# partial_vna.net
KiCad netlist of a schematic drawn in Altium Designer
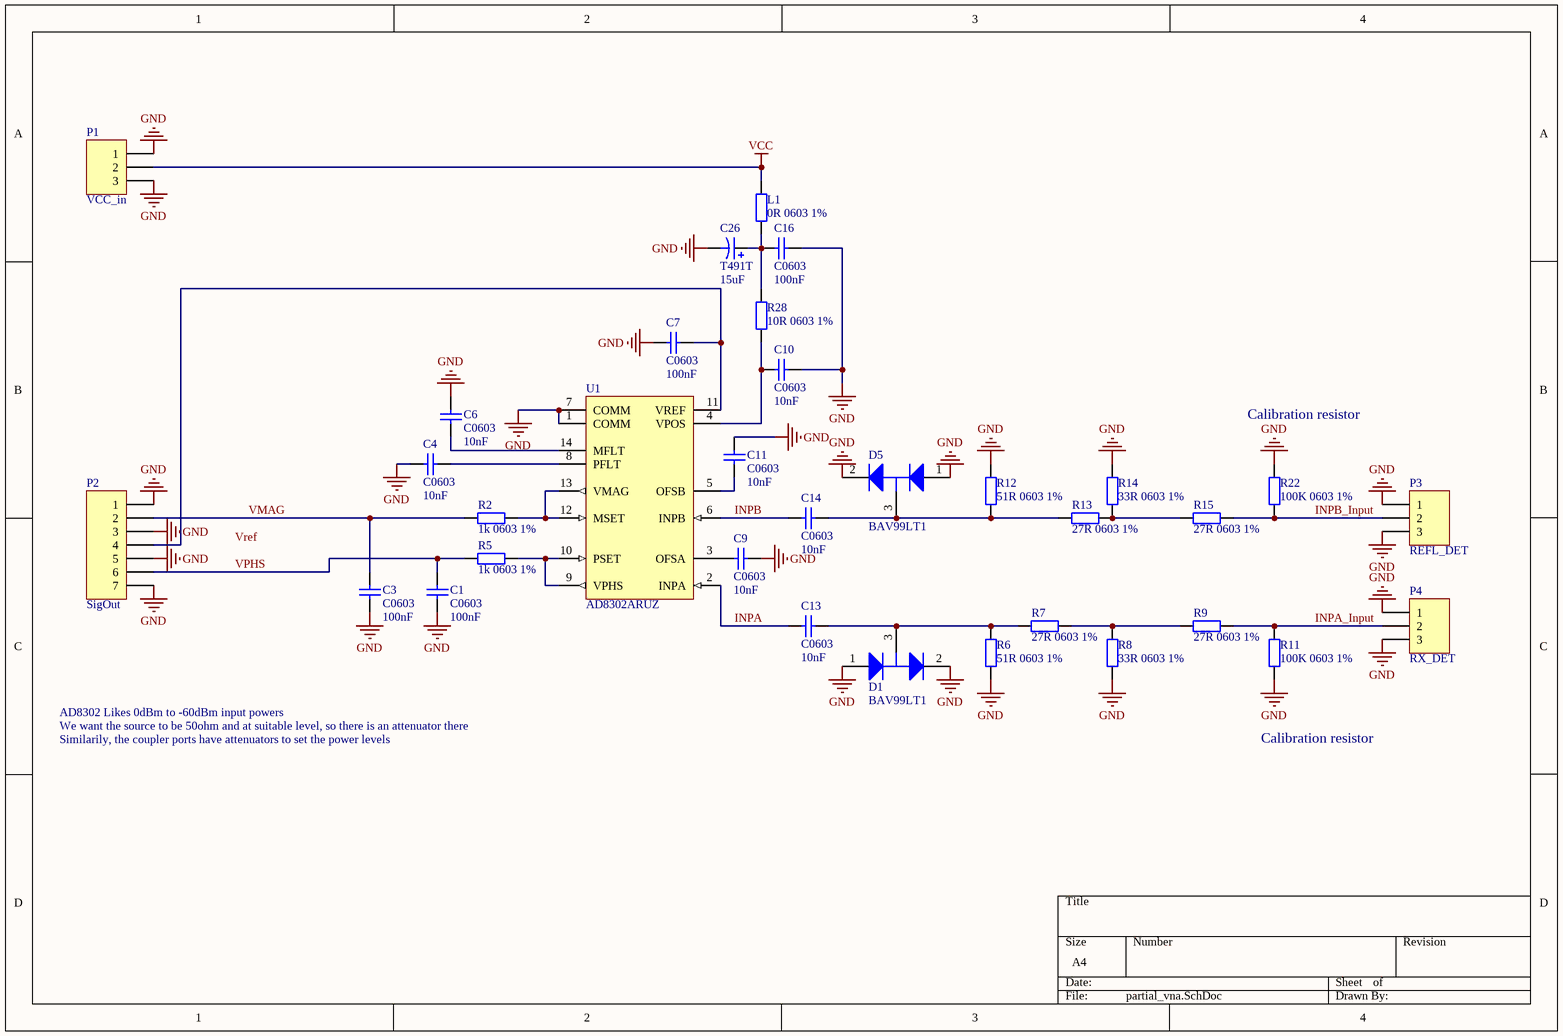
[diagram p0: partial_vna.SchDoc]

(export (version "E")
  (design (tool "Eeschema 10.0.6"))
  (components
    (comp (ref "C1")
      (value "C0603")
      (footprint "0603")
      (description "Ceramic Chip Capacitor - Standard")
      (fields (field (name "ALTIUM_VALUE") "100nF") (field (name "PUBLISHER") "Altium Limited"))
      (libsource (lib "KEMET Chip Capacitor") (part "C0603"))
    )
    (comp (ref "C3")
      (value "C0603")
      (footprint "0603")
      (description "Ceramic Chip Capacitor - Standard")
      (fields (field (name "ALTIUM_VALUE") "100nF") (field (name "PUBLISHER") "Altium Limited"))
      (libsource (lib "KEMET Chip Capacitor") (part "C0603"))
    )
    (comp (ref "C4")
      (value "C0603")
      (footprint "0603")
      (description "Ceramic Chip Capacitor - Standard")
      (fields (field (name "ALTIUM_VALUE") "10nF") (field (name "PUBLISHER") "Altium Limited"))
      (libsource (lib "KEMET Chip Capacitor") (part "C0603"))
    )
    (comp (ref "C6")
      (value "C0603")
      (footprint "0603")
      (description "Ceramic Chip Capacitor - Standard")
      (fields (field (name "ALTIUM_VALUE") "10nF") (field (name "PUBLISHER") "Altium Limited"))
      (libsource (lib "KEMET Chip Capacitor") (part "C0603"))
    )
    (comp (ref "C7")
      (value "C0603")
      (footprint "0603")
      (description "Ceramic Chip Capacitor - Standard")
      (fields (field (name "ALTIUM_VALUE") "100nF") (field (name "PUBLISHER") "Altium Limited"))
      (libsource (lib "KEMET Chip Capacitor") (part "C0603"))
    )
    (comp (ref "C9")
      (value "C0603")
      (footprint "0603")
      (description "Ceramic Chip Capacitor - Standard")
      (fields (field (name "ALTIUM_VALUE") "10nF") (field (name "PUBLISHER") "Altium Limited"))
      (libsource (lib "KEMET Chip Capacitor") (part "C0603"))
    )
    (comp (ref "C10")
      (value "C0603")
      (footprint "0603")
      (description "Ceramic Chip Capacitor - Standard")
      (fields (field (name "ALTIUM_VALUE") "10nF") (field (name "PUBLISHER") "Altium Limited"))
      (libsource (lib "KEMET Chip Capacitor") (part "C0603"))
    )
    (comp (ref "C11")
      (value "C0603")
      (footprint "0603")
      (description "Ceramic Chip Capacitor - Standard")
      (fields (field (name "ALTIUM_VALUE") "10nF") (field (name "PUBLISHER") "Altium Limited"))
      (libsource (lib "KEMET Chip Capacitor") (part "C0603"))
    )
    (comp (ref "C13")
      (value "C0603")
      (footprint "0603")
      (description "Ceramic Chip Capacitor - Standard")
      (fields (field (name "ALTIUM_VALUE") "10nF") (field (name "PUBLISHER") "Altium Limited"))
      (libsource (lib "KEMET Chip Capacitor") (part "C0603"))
    )
    (comp (ref "C14")
      (value "C0603")
      (footprint "0603")
      (description "Ceramic Chip Capacitor - Standard")
      (fields (field (name "ALTIUM_VALUE") "10nF") (field (name "PUBLISHER") "Altium Limited"))
      (libsource (lib "KEMET Chip Capacitor") (part "C0603"))
    )
    (comp (ref "C16")
      (value "C0603")
      (footprint "0603")
      (description "Ceramic Chip Capacitor - Standard")
      (fields (field (name "ALTIUM_VALUE") "100nF") (field (name "PUBLISHER") "Altium Limited"))
      (libsource (lib "KEMET Chip Capacitor") (part "C0603"))
    )
    (comp (ref "C26")
      (value "T491T")
      (footprint "T")
      (description "Solid Tantalum Chip Capacitor, Low Profile T491 Series - Industrial Grade")
      (fields (field (name "ALTIUM_VALUE") "15uF") (field (name "PUBLISHER") "Altium Limited"))
      (libsource (lib "KEMET Chip Capacitor") (part "T491T"))
    )
    (comp (ref "D1")
      (value "BAV99LT1")
      (footprint "ONSC-SOT-23-3-318-08_V")
      (description "Dual Series Switching Diodes, 3-Pin SOT-23, Tape and Reel")
      (fields (field (name "MANUFACTURER") "On Semiconductor"))
      (libsource (lib "ON Semi Small Signal Switching Diodes") (part "BAV99LT1"))
    )
    (comp (ref "D5")
      (value "BAV99LT1")
      (footprint "ONSC-SOT-23-3-318-08_V")
      (description "Dual Series Switching Diodes, 3-Pin SOT-23, Tape and Reel")
      (fields (field (name "MANUFACTURER") "On Semiconductor"))
      (libsource (lib "ON Semi Small Signal Switching Diodes") (part "BAV99LT1"))
    )
    (comp (ref "L1")
      (value "0R 0603 1%")
      (footprint "R0603")
      (fields (field (name "TOLERANCE") "1%") (field (name "PUBLISHER") "iv"))
      (libsource (lib "ftg_lib") (part "0R 0603"))
    )
    (comp (ref "P1")
      (value "VCC_in")
      (footprint "HDR1X3")
      (description "Header, 3-Pin")
      (fields (field (name "PUBLISHER") "Altium Limited"))
      (libsource (lib "") (part "Header 3_1"))
    )
    (comp (ref "P2")
      (value "SigOut")
      (footprint "HDR1X7")
      (description "Header, 7-Pin")
      (fields (field (name "PUBLISHER") "Altium Limited"))
      (libsource (lib "Miscellaneous Connectors") (part "Header 7"))
    )
    (comp (ref "P3")
      (value "REFL_DET")
      (footprint "HDR1X3")
      (description "Header, 3-Pin")
      (fields (field (name "PUBLISHER") "Altium Limited"))
      (libsource (lib "Miscellaneous Connectors") (part "Header 3"))
    )
    (comp (ref "P4")
      (value "RX_DET")
      (footprint "HDR1X3")
      (description "Header, 3-Pin")
      (fields (field (name "PUBLISHER") "Altium Limited"))
      (libsource (lib "Miscellaneous Connectors") (part "Header 3"))
    )
    (comp (ref "R2")
      (value "1k 0603 1%")
      (footprint "R0603")
      (fields (field (name "TOLERANCE") "1%") (field (name "PUBLISHER") "iv"))
      (libsource (lib "ftg_lib") (part "RES 1k 0603"))
    )
    (comp (ref "R5")
      (value "1k 0603 1%")
      (footprint "R0603")
      (fields (field (name "TOLERANCE") "1%") (field (name "PUBLISHER") "iv"))
      (libsource (lib "ftg_lib") (part "RES 1k 0603"))
    )
    (comp (ref "R6")
      (value "51R 0603 1%")
      (footprint "R0603")
      (fields (field (name "TOLERANCE") "1%") (field (name "PUBLISHER") "iv"))
      (libsource (lib "ftg_lib") (part "RES 51R 0603"))
    )
    (comp (ref "R7")
      (value "27R 0603 1%")
      (footprint "R0603")
      (fields (field (name "TOLERANCE") "1%") (field (name "PUBLISHER") "iv"))
      (libsource (lib "ftg_lib") (part "RES 27R 0603"))
    )
    (comp (ref "R8")
      (value "33R 0603 1%")
      (footprint "R0603")
      (fields (field (name "TOLERANCE") "1%") (field (name "PUBLISHER") "iv"))
      (libsource (lib "ftg_lib") (part "RES 33R 0603"))
    )
    (comp (ref "R9")
      (value "27R 0603 1%")
      (footprint "R0603")
      (fields (field (name "TOLERANCE") "1%") (field (name "PUBLISHER") "iv"))
      (libsource (lib "ftg_lib") (part "RES 27R 0603"))
    )
    (comp (ref "R11")
      (value "100K 0603 1%")
      (footprint "R0603")
      (fields (field (name "TOLERANCE") "1%") (field (name "PUBLISHER") "iv"))
      (libsource (lib "ftg_lib") (part "RES 100K 0603"))
    )
    (comp (ref "R12")
      (value "51R 0603 1%")
      (footprint "R0603")
      (fields (field (name "TOLERANCE") "1%") (field (name "PUBLISHER") "iv"))
      (libsource (lib "ftg_lib") (part "RES 51R 0603"))
    )
    (comp (ref "R13")
      (value "27R 0603 1%")
      (footprint "R0603")
      (fields (field (name "TOLERANCE") "1%") (field (name "PUBLISHER") "iv"))
      (libsource (lib "ftg_lib") (part "RES 27R 0603"))
    )
    (comp (ref "R14")
      (value "33R 0603 1%")
      (footprint "R0603")
      (fields (field (name "TOLERANCE") "1%") (field (name "PUBLISHER") "iv"))
      (libsource (lib "ftg_lib") (part "RES 33R 0603"))
    )
    (comp (ref "R15")
      (value "27R 0603 1%")
      (footprint "R0603")
      (fields (field (name "TOLERANCE") "1%") (field (name "PUBLISHER") "iv"))
      (libsource (lib "ftg_lib") (part "RES 27R 0603"))
    )
    (comp (ref "R22")
      (value "100K 0603 1%")
      (footprint "R0603")
      (fields (field (name "TOLERANCE") "1%") (field (name "PUBLISHER") "iv"))
      (libsource (lib "ftg_lib") (part "RES 100K 0603"))
    )
    (comp (ref "R28")
      (value "10R 0603 1%")
      (footprint "R0603")
      (fields (field (name "TOLERANCE") "1%") (field (name "PUBLISHER") "iv"))
      (libsource (lib "ftg_lib") (part "RES 10R 0603"))
    )
    (comp (ref "U1")
      (value "AD8302ARUZ")
      (footprint "ADI-RU-14_L")
      (description "LF-2.7 GHz RF/IF Gain and Phase Detector, 60ns Response Time, RU-14, Pb-Free, 96 Tube")
      (libsource (lib "Altium Content Vault") (part "ADI-AD8302-RU-14"))
    )
  )
  (nets
    (net (code "1") (name "/INPA") (class "Default")
      (node (ref "C13") (pin "2") (pinfunction "2_2") (pintype "passive"))
      (node (ref "U1") (pin "2") (pinfunction "INPA_2") (pintype "input"))
    )
    (net (code "2") (name "/INPA_Input") (class "Default")
      (node (ref "P4") (pin "2") (pinfunction "2_2") (pintype "passive"))
      (node (ref "R11") (pin "2") (pinfunction "2_2") (pintype "passive"))
      (node (ref "R9") (pin "2") (pinfunction "2_2") (pintype "passive"))
    )
    (net (code "3") (name "/INPB") (class "Default")
      (node (ref "C14") (pin "2") (pinfunction "2_2") (pintype "passive"))
      (node (ref "U1") (pin "6") (pinfunction "INPB_6") (pintype "input"))
    )
    (net (code "4") (name "/INPB_Input") (class "Default")
      (node (ref "P3") (pin "2") (pinfunction "2_2") (pintype "passive"))
      (node (ref "R15") (pin "2") (pinfunction "2_2") (pintype "passive"))
      (node (ref "R22") (pin "1") (pinfunction "1_1") (pintype "passive"))
    )
    (net (code "5") (name "/VMAG") (class "Default")
      (node (ref "C3") (pin "2") (pinfunction "2_2") (pintype "passive"))
      (node (ref "P2") (pin "2") (pinfunction "2_2") (pintype "passive"))
      (node (ref "R2") (pin "1") (pinfunction "1_1") (pintype "passive"))
    )
    (net (code "6") (name "/VPHS") (class "Default")
      (node (ref "C1") (pin "2") (pinfunction "2_2") (pintype "passive"))
      (node (ref "P2") (pin "6") (pinfunction "6_6") (pintype "passive"))
      (node (ref "R5") (pin "1") (pinfunction "1_1") (pintype "passive"))
    )
    (net (code "8") (name "GND") (class "Default")
      (node (ref "C1") (pin "1") (pinfunction "1_1") (pintype "passive"))
      (node (ref "C10") (pin "2") (pinfunction "2_2") (pintype "passive"))
      (node (ref "C11") (pin "1") (pinfunction "1_1") (pintype "passive"))
      (node (ref "C16") (pin "2") (pinfunction "2_2") (pintype "passive"))
      (node (ref "C26") (pin "2") (pinfunction "2_2") (pintype "passive"))
      (node (ref "C3") (pin "1") (pinfunction "1_1") (pintype "passive"))
      (node (ref "C4") (pin "2") (pinfunction "2_2") (pintype "passive"))
      (node (ref "C6") (pin "2") (pinfunction "2_2") (pintype "passive"))
      (node (ref "C7") (pin "2") (pinfunction "2_2") (pintype "passive"))
      (node (ref "C9") (pin "1") (pinfunction "1_1") (pintype "passive"))
      (node (ref "D1") (pin "1") (pinfunction "A_1") (pintype "passive"))
      (node (ref "D1") (pin "2") (pinfunction "K_2") (pintype "passive"))
      (node (ref "D5") (pin "1") (pinfunction "A_1") (pintype "passive"))
      (node (ref "D5") (pin "2") (pinfunction "K_2") (pintype "passive"))
      (node (ref "P1") (pin "1") (pinfunction "1_1") (pintype "passive"))
      (node (ref "P1") (pin "3") (pinfunction "3_3") (pintype "passive"))
      (node (ref "P2") (pin "1") (pinfunction "1_1") (pintype "passive"))
      (node (ref "P2") (pin "3") (pinfunction "3_3") (pintype "passive"))
      (node (ref "P2") (pin "5") (pinfunction "5_5") (pintype "passive"))
      (node (ref "P2") (pin "7") (pinfunction "7_7") (pintype "passive"))
      (node (ref "P3") (pin "1") (pinfunction "1_1") (pintype "passive"))
      (node (ref "P3") (pin "3") (pinfunction "3_3") (pintype "passive"))
      (node (ref "P4") (pin "1") (pinfunction "1_1") (pintype "passive"))
      (node (ref "P4") (pin "3") (pinfunction "3_3") (pintype "passive"))
      (node (ref "R11") (pin "1") (pinfunction "1_1") (pintype "passive"))
      (node (ref "R12") (pin "2") (pinfunction "2_2") (pintype "passive"))
      (node (ref "R14") (pin "2") (pinfunction "2_2") (pintype "passive"))
      (node (ref "R22") (pin "2") (pinfunction "2_2") (pintype "passive"))
      (node (ref "R6") (pin "1") (pinfunction "1_1") (pintype "passive"))
      (node (ref "R8") (pin "1") (pinfunction "1_1") (pintype "passive"))
      (node (ref "U1") (pin "1") (pinfunction "COMM_1") (pintype "power_in"))
      (node (ref "U1") (pin "7") (pinfunction "COMM_7") (pintype "power_in"))
    )
    (net (code "9") (name "Net-(C16-Pad1)") (class "Default")
      (node (ref "C16") (pin "1") (pinfunction "1_1") (pintype "passive"))
      (node (ref "C26") (pin "1") (pinfunction "1_1") (pintype "passive"))
      (node (ref "L1") (pin "1") (pinfunction "1_1") (pintype "passive"))
      (node (ref "R28") (pin "2") (pinfunction "2_2") (pintype "passive"))
    )
    (net (code "10") (name "Net-(D1-K{slash}A)") (class "Default")
      (node (ref "C13") (pin "1") (pinfunction "1_1") (pintype "passive"))
      (node (ref "D1") (pin "3") (pinfunction "K/A_3") (pintype "passive"))
      (node (ref "R6") (pin "2") (pinfunction "2_2") (pintype "passive"))
      (node (ref "R7") (pin "1") (pinfunction "1_1") (pintype "passive"))
    )
    (net (code "11") (name "Net-(D5-K{slash}A)") (class "Default")
      (node (ref "C14") (pin "1") (pinfunction "1_1") (pintype "passive"))
      (node (ref "D5") (pin "3") (pinfunction "K/A_3") (pintype "passive"))
      (node (ref "R12") (pin "1") (pinfunction "1_1") (pintype "passive"))
      (node (ref "R13") (pin "1") (pinfunction "1_1") (pintype "passive"))
    )
    (net (code "12") (name "Net-(R7-Pad2)") (class "Default")
      (node (ref "R7") (pin "2") (pinfunction "2_2") (pintype "passive"))
      (node (ref "R8") (pin "2") (pinfunction "2_2") (pintype "passive"))
      (node (ref "R9") (pin "1") (pinfunction "1_1") (pintype "passive"))
    )
    (net (code "13") (name "Net-(R13-Pad2)") (class "Default")
      (node (ref "R13") (pin "2") (pinfunction "2_2") (pintype "passive"))
      (node (ref "R14") (pin "1") (pinfunction "1_1") (pintype "passive"))
      (node (ref "R15") (pin "1") (pinfunction "1_1") (pintype "passive"))
    )
    (net (code "14") (name "Net-(U1-MFLT)") (class "Default")
      (node (ref "C6") (pin "1") (pinfunction "1_1") (pintype "passive"))
      (node (ref "U1") (pin "14") (pinfunction "MFLT_14") (pintype "passive"))
    )
    (net (code "15") (name "Net-(U1-MSET)") (class "Default")
      (node (ref "R2") (pin "2") (pinfunction "2_2") (pintype "passive"))
      (node (ref "U1") (pin "12") (pinfunction "MSET_12") (pintype "input"))
      (node (ref "U1") (pin "13") (pinfunction "VMAG_13") (pintype "output"))
    )
    (net (code "16") (name "Net-(U1-OFSA)") (class "Default")
      (node (ref "C9") (pin "2") (pinfunction "2_2") (pintype "passive"))
      (node (ref "U1") (pin "3") (pinfunction "OFSA_3") (pintype "passive"))
    )
    (net (code "17") (name "Net-(U1-OFSB)") (class "Default")
      (node (ref "C11") (pin "2") (pinfunction "2_2") (pintype "passive"))
      (node (ref "U1") (pin "5") (pinfunction "OFSB_5") (pintype "passive"))
    )
    (net (code "18") (name "Net-(U1-PFLT)") (class "Default")
      (node (ref "C4") (pin "1") (pinfunction "1_1") (pintype "passive"))
      (node (ref "U1") (pin "8") (pinfunction "PFLT_8") (pintype "passive"))
    )
    (net (code "19") (name "Net-(U1-PSET)") (class "Default")
      (node (ref "R5") (pin "2") (pinfunction "2_2") (pintype "passive"))
      (node (ref "U1") (pin "10") (pinfunction "PSET_10") (pintype "input"))
      (node (ref "U1") (pin "9") (pinfunction "VPHS_9") (pintype "output"))
    )
    (net (code "20") (name "Net-(U1-VPOS)") (class "Default")
      (node (ref "C10") (pin "1") (pinfunction "1_1") (pintype "passive"))
      (node (ref "R28") (pin "1") (pinfunction "1_1") (pintype "passive"))
      (node (ref "U1") (pin "4") (pinfunction "VPOS_4") (pintype "power_in"))
    )
    (net (code "21") (name "Net-(U1-VREF)") (class "Default")
      (node (ref "C7") (pin "1") (pinfunction "1_1") (pintype "passive"))
      (node (ref "P2") (pin "4") (pinfunction "4_4") (pintype "passive"))
      (node (ref "U1") (pin "11") (pinfunction "VREF_11") (pintype "power_in"))
    )
    (net (code "22") (name "VCC") (class "Default")
      (node (ref "L1") (pin "2") (pinfunction "2_2") (pintype "passive"))
      (node (ref "P1") (pin "2") (pinfunction "2_2") (pintype "passive"))
    )
  )
)
